# ASD2163.net
KiCad netlist of a schematic drawn in EAGLE
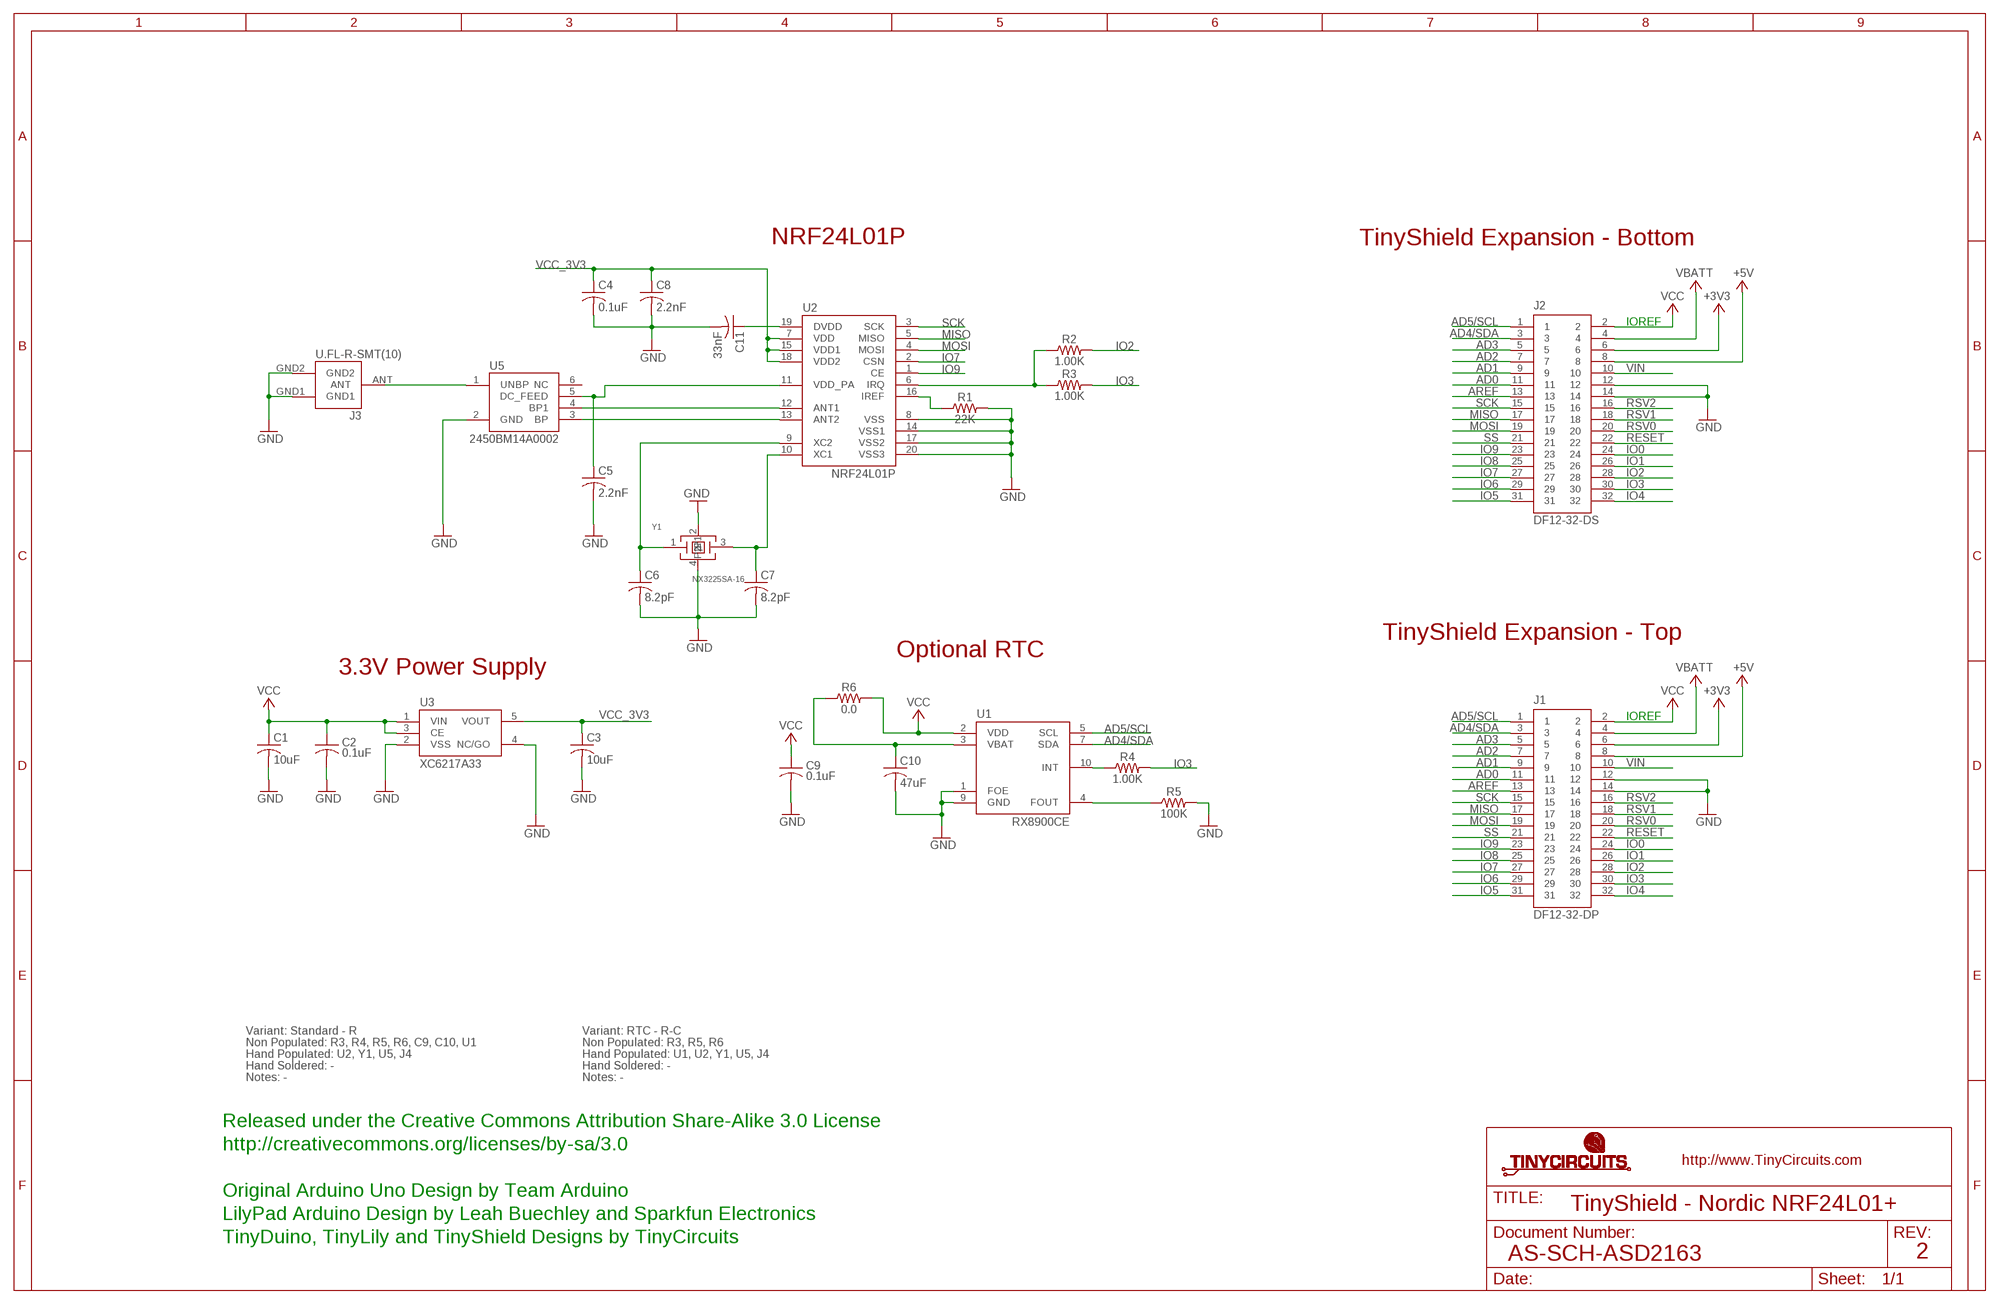
[diagram p0: schematic, sheet 1]

(export (version "E")
  (design (tool "Eeschema 10.0.6"))
  (components
    (comp (ref "C1")
      (value "10uF")
      (footprint "eagle-import:C0603")
      (fields (field (name "PARTNO") "AS-ITM-00002") (field (name "PARTNO_1") "AS-ITM-00002"))
      (libsource (lib "eagle-import") (part "AS-ITM-00002"))
    )
    (comp (ref "C2")
      (value "0.1uF")
      (footprint "eagle-import:C0402")
      (fields (field (name "PARTNO") "AS-ITM-00008") (field (name "PARTNO_1") "AS-ITM-00008"))
      (libsource (lib "eagle-import") (part "AS-ITM-00008"))
    )
    (comp (ref "C3")
      (value "10uF")
      (footprint "eagle-import:C0603")
      (fields (field (name "PARTNO") "AS-ITM-00002") (field (name "PARTNO_1") "AS-ITM-00002"))
      (libsource (lib "eagle-import") (part "AS-ITM-00002"))
    )
    (comp (ref "C4")
      (value "0.1uF")
      (footprint "eagle-import:C0402")
      (fields (field (name "PARTNO") "AS-ITM-00008") (field (name "PARTNO_1") "AS-ITM-00008"))
      (libsource (lib "eagle-import") (part "AS-ITM-00008"))
    )
    (comp (ref "C5")
      (value "2.2nF")
      (footprint "eagle-import:C0402")
      (fields (field (name "PARTNO") "AS-ITM-00085"))
      (libsource (lib "eagle-import") (part "AS-ITM-00085"))
    )
    (comp (ref "C6")
      (value "8.2pF")
      (footprint "eagle-import:C0402")
      (fields (field (name "PARTNO") "AS-ITM-00247") (field (name "PARTNO_1") "AS-ITM-00247"))
      (libsource (lib "eagle-import") (part "AS-ITM-00247"))
    )
    (comp (ref "C7")
      (value "8.2pF")
      (footprint "eagle-import:C0402")
      (fields (field (name "PARTNO") "AS-ITM-00247") (field (name "PARTNO_1") "AS-ITM-00247"))
      (libsource (lib "eagle-import") (part "AS-ITM-00247"))
    )
    (comp (ref "C8")
      (value "2.2nF")
      (footprint "eagle-import:C0402")
      (fields (field (name "PARTNO") "AS-ITM-00085") (field (name "PARTNO_1") "AS-ITM-00085"))
      (libsource (lib "eagle-import") (part "AS-ITM-00085"))
    )
    (comp (ref "C9")
      (value "0.1uF")
      (footprint "eagle-import:C0402")
      (fields (field (name "PARTNO") "AS-ITM-00008") (field (name "PARTNO_1") "AS-ITM-00008"))
      (libsource (lib "eagle-import") (part "AS-ITM-00008"))
    )
    (comp (ref "C10")
      (value "47uF")
      (footprint "eagle-import:C1206")
      (fields (field (name "PARTNO") "AS-ITM-00049"))
      (libsource (lib "eagle-import") (part "AS-ITM-00049"))
    )
    (comp (ref "C11")
      (value "33nF")
      (footprint "eagle-import:C0402")
      (fields (field (name "PARTNO") "AS-ITM-00248") (field (name "PARTNO_1") "AS-ITM-00248"))
      (libsource (lib "eagle-import") (part "AS-ITM-00248"))
    )
    (comp (ref "J1")
      (value "DF12-32-DP")
      (footprint "eagle-import:DF12-32-DP")
      (fields (field (name "PARTNO") "AS-ITM-00015") (field (name "PARTNO_1") "AS-ITM-00015"))
      (libsource (lib "eagle-import") (part "AS-ITM-00015"))
    )
    (comp (ref "J2")
      (value "DF12-32-DS")
      (footprint "eagle-import:DF12-32-DS")
      (fields (field (name "PARTNO") "AS-ITM-00012") (field (name "PARTNO_1") "AS-ITM-00012"))
      (libsource (lib "eagle-import") (part "AS-ITM-00012"))
    )
    (comp (ref "J3")
      (value "U.FL-R-SMT(10)")
      (footprint "eagle-import:U.FL-R-SMT(10)")
      (fields (field (name "PARTNO") "AS-ITM-00193"))
      (libsource (lib "eagle-import") (part "AS-ITM-00193"))
    )
    (comp (ref "R1")
      (value "22K")
      (footprint "eagle-import:0402")
      (fields (field (name "PARTNO") "AS-ITM-00147"))
      (libsource (lib "eagle-import") (part "AS-ITM-00147"))
    )
    (comp (ref "R2")
      (value "1.00K")
      (footprint "eagle-import:0402")
      (fields (field (name "PARTNO") "AS-ITM-00003") (field (name "PARTNO_1") "AS-ITM-00003"))
      (libsource (lib "eagle-import") (part "AS-ITM-00003"))
    )
    (comp (ref "R3")
      (value "1.00K")
      (footprint "eagle-import:0402")
      (fields (field (name "PARTNO") "AS-ITM-00003") (field (name "PARTNO_1") "AS-ITM-00003"))
      (libsource (lib "eagle-import") (part "AS-ITM-00003"))
    )
    (comp (ref "R4")
      (value "1.00K")
      (footprint "eagle-import:0402")
      (fields (field (name "PARTNO") "AS-ITM-00003") (field (name "PARTNO_1") "AS-ITM-00003"))
      (libsource (lib "eagle-import") (part "AS-ITM-00003"))
    )
    (comp (ref "R5")
      (value "100K")
      (footprint "eagle-import:0402")
      (fields (field (name "PARTNO") "AS-ITM-00004"))
      (libsource (lib "eagle-import") (part "AS-ITM-00004"))
    )
    (comp (ref "R6")
      (value "0.0")
      (footprint "eagle-import:0402")
      (fields (field (name "PARTNO") "AS-ITM-00076") (field (name "PARTNO_1") "AS-ITM-00076"))
      (libsource (lib "eagle-import") (part "AS-ITM-00076"))
    )
    (comp (ref "U1")
      (value "RX8900CE")
      (footprint "eagle-import:RX8900CE")
      (fields (field (name "PARTNO") "AS-ITM-00373"))
      (libsource (lib "eagle-import") (part "AS-ITM-00373"))
    )
    (comp (ref "U2")
      (value "NRF24L01P")
      (footprint "eagle-import:QFN20-NO_PAD")
      (fields (field (name "PARTNO") "AS-ITM-00276"))
      (libsource (lib "eagle-import") (part "AS-ITM-00276"))
    )
    (comp (ref "U3")
      (value "XC6217A33")
      (footprint "eagle-import:SOT-25")
      (fields (field (name "PARTNO") "AS-ITM-00249") (field (name "PARTNO_1") "AS-ITM-00249"))
      (libsource (lib "eagle-import") (part "AS-ITM-00249"))
    )
    (comp (ref "U5")
      (value "2450BM14A0002")
      (footprint "eagle-import:2450BM14A0002")
      (fields (field (name "PARTNO") "AS-ITM-00114"))
      (libsource (lib "eagle-import") (part "AS-ITM-00114"))
    )
    (comp (ref "Y1")
      (value "NX3225SA-16")
      (footprint "eagle-import:ABM11")
      (fields (field (name "PARTNO") "AS-ITM-00228") (field (name "PARTNO_1") "AS-ITM-00228"))
      (libsource (lib "eagle-import") (part "AS-ITM-00228"))
    )
  )
  (nets
    (net (code "1") (name "+3V3") (class "Default")
      (node (ref "J1") (pin "6") (pinfunction "6_6") (pintype "bidirectional"))
      (node (ref "J2") (pin "6") (pinfunction "6_6") (pintype "bidirectional"))
    )
    (net (code "2") (name "+5V") (class "Default")
      (node (ref "J1") (pin "8") (pinfunction "8_8") (pintype "bidirectional"))
      (node (ref "J2") (pin "8") (pinfunction "8_8") (pintype "bidirectional"))
    )
    (net (code "3") (name "/AD0") (class "Default")
      (node (ref "J1") (pin "11") (pinfunction "11_11") (pintype "bidirectional"))
      (node (ref "J2") (pin "11") (pinfunction "11_11") (pintype "bidirectional"))
    )
    (net (code "4") (name "/AD1") (class "Default")
      (node (ref "J1") (pin "9") (pinfunction "9_9") (pintype "bidirectional"))
      (node (ref "J2") (pin "9") (pinfunction "9_9") (pintype "bidirectional"))
    )
    (net (code "5") (name "/AD2") (class "Default")
      (node (ref "J1") (pin "7") (pinfunction "7_7") (pintype "bidirectional"))
      (node (ref "J2") (pin "7") (pinfunction "7_7") (pintype "bidirectional"))
    )
    (net (code "6") (name "/AD3") (class "Default")
      (node (ref "J1") (pin "5") (pinfunction "5_5") (pintype "bidirectional"))
      (node (ref "J2") (pin "5") (pinfunction "5_5") (pintype "bidirectional"))
    )
    (net (code "7") (name "/AD4{slash}SDA") (class "Default")
      (node (ref "J1") (pin "3") (pinfunction "3_3") (pintype "bidirectional"))
      (node (ref "J2") (pin "3") (pinfunction "3_3") (pintype "bidirectional"))
      (node (ref "U1") (pin "7") (pinfunction "SDA_7") (pintype "bidirectional"))
    )
    (net (code "8") (name "/AD5{slash}SCL") (class "Default")
      (node (ref "J1") (pin "1") (pinfunction "1_1") (pintype "bidirectional"))
      (node (ref "J2") (pin "1") (pinfunction "1_1") (pintype "bidirectional"))
      (node (ref "U1") (pin "5") (pinfunction "SCL_5") (pintype "bidirectional"))
    )
    (net (code "9") (name "/AREF") (class "Default")
      (node (ref "J1") (pin "13") (pinfunction "13_13") (pintype "bidirectional"))
      (node (ref "J2") (pin "13") (pinfunction "13_13") (pintype "bidirectional"))
    )
    (net (code "10") (name "/IO0") (class "Default")
      (node (ref "J1") (pin "24") (pinfunction "24_24") (pintype "bidirectional"))
      (node (ref "J2") (pin "24") (pinfunction "24_24") (pintype "bidirectional"))
    )
    (net (code "11") (name "/IO1") (class "Default")
      (node (ref "J1") (pin "26") (pinfunction "26_26") (pintype "bidirectional"))
      (node (ref "J2") (pin "26") (pinfunction "26_26") (pintype "bidirectional"))
    )
    (net (code "12") (name "/IO2") (class "Default")
      (node (ref "J1") (pin "28") (pinfunction "28_28") (pintype "bidirectional"))
      (node (ref "J2") (pin "28") (pinfunction "28_28") (pintype "bidirectional"))
      (node (ref "R2") (pin "2") (pinfunction "2_2") (pintype "passive"))
    )
    (net (code "13") (name "/IO3") (class "Default")
      (node (ref "J1") (pin "30") (pinfunction "30_30") (pintype "bidirectional"))
      (node (ref "J2") (pin "30") (pinfunction "30_30") (pintype "bidirectional"))
      (node (ref "R3") (pin "2") (pinfunction "2_2") (pintype "passive"))
      (node (ref "R4") (pin "2") (pinfunction "2_2") (pintype "passive"))
    )
    (net (code "14") (name "/IO4") (class "Default")
      (node (ref "J1") (pin "32") (pinfunction "32_32") (pintype "bidirectional"))
      (node (ref "J2") (pin "32") (pinfunction "32_32") (pintype "bidirectional"))
    )
    (net (code "15") (name "/IO5") (class "Default")
      (node (ref "J1") (pin "31") (pinfunction "31_31") (pintype "bidirectional"))
      (node (ref "J2") (pin "31") (pinfunction "31_31") (pintype "bidirectional"))
    )
    (net (code "16") (name "/IO6") (class "Default")
      (node (ref "J1") (pin "29") (pinfunction "29_29") (pintype "bidirectional"))
      (node (ref "J2") (pin "29") (pinfunction "29_29") (pintype "bidirectional"))
    )
    (net (code "17") (name "/IO7") (class "Default")
      (node (ref "J1") (pin "27") (pinfunction "27_27") (pintype "bidirectional"))
      (node (ref "J2") (pin "27") (pinfunction "27_27") (pintype "bidirectional"))
      (node (ref "U2") (pin "2") (pinfunction "CSN_2") (pintype "bidirectional"))
    )
    (net (code "18") (name "/IO8") (class "Default")
      (node (ref "J1") (pin "25") (pinfunction "25_25") (pintype "bidirectional"))
      (node (ref "J2") (pin "25") (pinfunction "25_25") (pintype "bidirectional"))
    )
    (net (code "19") (name "/IO9") (class "Default")
      (node (ref "J1") (pin "23") (pinfunction "23_23") (pintype "bidirectional"))
      (node (ref "J2") (pin "23") (pinfunction "23_23") (pintype "bidirectional"))
      (node (ref "U2") (pin "1") (pinfunction "CE_1") (pintype "bidirectional"))
    )
    (net (code "20") (name "/MISO") (class "Default")
      (node (ref "J1") (pin "17") (pinfunction "17_17") (pintype "bidirectional"))
      (node (ref "J2") (pin "17") (pinfunction "17_17") (pintype "bidirectional"))
      (node (ref "U2") (pin "5") (pinfunction "MISO_5") (pintype "bidirectional"))
    )
    (net (code "21") (name "/MOSI") (class "Default")
      (node (ref "J1") (pin "19") (pinfunction "19_19") (pintype "bidirectional"))
      (node (ref "J2") (pin "19") (pinfunction "19_19") (pintype "bidirectional"))
      (node (ref "U2") (pin "4") (pinfunction "MOSI_4") (pintype "bidirectional"))
    )
    (net (code "22") (name "/RESET") (class "Default")
      (node (ref "J1") (pin "22") (pinfunction "22_22") (pintype "bidirectional"))
      (node (ref "J2") (pin "22") (pinfunction "22_22") (pintype "bidirectional"))
    )
    (net (code "23") (name "/RSV0") (class "Default")
      (node (ref "J1") (pin "20") (pinfunction "20_20") (pintype "bidirectional"))
      (node (ref "J2") (pin "20") (pinfunction "20_20") (pintype "bidirectional"))
    )
    (net (code "24") (name "/RSV1") (class "Default")
      (node (ref "J1") (pin "18") (pinfunction "18_18") (pintype "bidirectional"))
      (node (ref "J2") (pin "18") (pinfunction "18_18") (pintype "bidirectional"))
    )
    (net (code "25") (name "/RSV2") (class "Default")
      (node (ref "J1") (pin "16") (pinfunction "16_16") (pintype "bidirectional"))
      (node (ref "J2") (pin "16") (pinfunction "16_16") (pintype "bidirectional"))
    )
    (net (code "26") (name "/SCK") (class "Default")
      (node (ref "J1") (pin "15") (pinfunction "15_15") (pintype "bidirectional"))
      (node (ref "J2") (pin "15") (pinfunction "15_15") (pintype "bidirectional"))
      (node (ref "U2") (pin "3") (pinfunction "SCK_3") (pintype "bidirectional"))
    )
    (net (code "27") (name "/SS") (class "Default")
      (node (ref "J1") (pin "21") (pinfunction "21_21") (pintype "bidirectional"))
      (node (ref "J2") (pin "21") (pinfunction "21_21") (pintype "bidirectional"))
    )
    (net (code "28") (name "/VCC_3V3") (class "Default")
      (node (ref "C3") (pin "1") (pinfunction "1_1") (pintype "passive"))
      (node (ref "C4") (pin "1") (pinfunction "1_1") (pintype "passive"))
      (node (ref "C8") (pin "1") (pinfunction "1_1") (pintype "passive"))
      (node (ref "U2") (pin "15") (pinfunction "VDD1_15") (pintype "bidirectional"))
      (node (ref "U2") (pin "18") (pinfunction "VDD2_18") (pintype "bidirectional"))
      (node (ref "U2") (pin "7") (pinfunction "VDD_7") (pintype "bidirectional"))
      (node (ref "U3") (pin "5") (pinfunction "VOUT_5") (pintype "bidirectional"))
    )
    (net (code "29") (name "/VIN") (class "Default")
      (node (ref "J1") (pin "10") (pinfunction "10_10") (pintype "bidirectional"))
      (node (ref "J2") (pin "10") (pinfunction "10_10") (pintype "bidirectional"))
    )
    (net (code "30") (name "GND") (class "Default")
      (node (ref "C1") (pin "2") (pinfunction "2_2") (pintype "passive"))
      (node (ref "C10") (pin "2") (pinfunction "2_2") (pintype "passive"))
      (node (ref "C11") (pin "2") (pinfunction "2_2") (pintype "passive"))
      (node (ref "C2") (pin "2") (pinfunction "2_2") (pintype "passive"))
      (node (ref "C3") (pin "2") (pinfunction "2_2") (pintype "passive"))
      (node (ref "C4") (pin "2") (pinfunction "2_2") (pintype "passive"))
      (node (ref "C5") (pin "2") (pinfunction "2_2") (pintype "passive"))
      (node (ref "C6") (pin "2") (pinfunction "2_2") (pintype "passive"))
      (node (ref "C7") (pin "2") (pinfunction "2_2") (pintype "passive"))
      (node (ref "C8") (pin "2") (pinfunction "2_2") (pintype "passive"))
      (node (ref "C9") (pin "2") (pinfunction "2_2") (pintype "passive"))
      (node (ref "J1") (pin "12") (pinfunction "12_12") (pintype "bidirectional"))
      (node (ref "J1") (pin "14") (pinfunction "14_14") (pintype "bidirectional"))
      (node (ref "J2") (pin "12") (pinfunction "12_12") (pintype "bidirectional"))
      (node (ref "J2") (pin "14") (pinfunction "14_14") (pintype "bidirectional"))
      (node (ref "J3") (pin "GND1") (pinfunction "GND1_GND1") (pintype "bidirectional"))
      (node (ref "J3") (pin "GND2") (pinfunction "GND2_GND2") (pintype "bidirectional"))
      (node (ref "R1") (pin "2") (pinfunction "2_2") (pintype "passive"))
      (node (ref "R5") (pin "2") (pinfunction "2_2") (pintype "passive"))
      (node (ref "U1") (pin "1") (pinfunction "FOE_1") (pintype "bidirectional"))
      (node (ref "U1") (pin "9") (pinfunction "GND_9") (pintype "bidirectional"))
      (node (ref "U2") (pin "14") (pinfunction "VSS1_14") (pintype "bidirectional"))
      (node (ref "U2") (pin "17") (pinfunction "VSS2_17") (pintype "bidirectional"))
      (node (ref "U2") (pin "20") (pinfunction "VSS3_20") (pintype "bidirectional"))
      (node (ref "U2") (pin "8") (pinfunction "VSS_8") (pintype "bidirectional"))
      (node (ref "U3") (pin "2") (pinfunction "VSS_2") (pintype "power_in"))
      (node (ref "U3") (pin "4") (pinfunction "NC/GO_4") (pintype "bidirectional"))
      (node (ref "U5") (pin "2") (pinfunction "GND_2") (pintype "bidirectional"))
      (node (ref "Y1") (pin "2") (pinfunction "P2_2") (pintype "bidirectional"))
      (node (ref "Y1") (pin "4") (pinfunction "P1_4") (pintype "bidirectional"))
    )
    (net (code "31") (name "Net-(U1-FOUT)") (class "Default")
      (node (ref "R5") (pin "1") (pinfunction "1_1") (pintype "passive"))
      (node (ref "U1") (pin "4") (pinfunction "FOUT_4") (pintype "bidirectional"))
    )
    (net (code "32") (name "Net-(U1-INT)") (class "Default")
      (node (ref "R4") (pin "1") (pinfunction "1_1") (pintype "passive"))
      (node (ref "U1") (pin "10") (pinfunction "INT_10") (pintype "bidirectional"))
    )
    (net (code "33") (name "Net-(U1-VBAT)") (class "Default")
      (node (ref "C10") (pin "1") (pinfunction "1_1") (pintype "passive"))
      (node (ref "R6") (pin "1") (pinfunction "1_1") (pintype "passive"))
      (node (ref "U1") (pin "3") (pinfunction "VBAT_3") (pintype "bidirectional"))
    )
    (net (code "34") (name "Net-(U2-ANT1)") (class "Default")
      (node (ref "U2") (pin "12") (pinfunction "ANT1_12") (pintype "bidirectional"))
      (node (ref "U5") (pin "4") (pinfunction "BP1_4") (pintype "bidirectional"))
    )
    (net (code "35") (name "Net-(U2-ANT2)") (class "Default")
      (node (ref "U2") (pin "13") (pinfunction "ANT2_13") (pintype "bidirectional"))
      (node (ref "U5") (pin "3") (pinfunction "BP_3") (pintype "bidirectional"))
    )
    (net (code "36") (name "Net-(U2-DVDD)") (class "Default")
      (node (ref "C11") (pin "1") (pinfunction "1_1") (pintype "passive"))
      (node (ref "U2") (pin "19") (pinfunction "DVDD_19") (pintype "bidirectional"))
    )
    (net (code "37") (name "Net-(U2-IREF)") (class "Default")
      (node (ref "R1") (pin "1") (pinfunction "1_1") (pintype "passive"))
      (node (ref "U2") (pin "16") (pinfunction "IREF_16") (pintype "bidirectional"))
    )
    (net (code "38") (name "Net-(U2-IRQ)") (class "Default")
      (node (ref "R2") (pin "1") (pinfunction "1_1") (pintype "passive"))
      (node (ref "R3") (pin "1") (pinfunction "1_1") (pintype "passive"))
      (node (ref "U2") (pin "6") (pinfunction "IRQ_6") (pintype "bidirectional"))
    )
    (net (code "39") (name "Net-(U2-VDD_PA)") (class "Default")
      (node (ref "C5") (pin "1") (pinfunction "1_1") (pintype "passive"))
      (node (ref "U2") (pin "11") (pinfunction "VDD_PA_11") (pintype "bidirectional"))
      (node (ref "U5") (pin "5") (pinfunction "DC_FEED_5") (pintype "bidirectional"))
    )
    (net (code "40") (name "Net-(U2-XC1)") (class "Default")
      (node (ref "C7") (pin "1") (pinfunction "1_1") (pintype "passive"))
      (node (ref "U2") (pin "10") (pinfunction "XC1_10") (pintype "bidirectional"))
      (node (ref "Y1") (pin "3") (pinfunction "2_3") (pintype "bidirectional"))
    )
    (net (code "41") (name "Net-(U2-XC2)") (class "Default")
      (node (ref "C6") (pin "1") (pinfunction "1_1") (pintype "passive"))
      (node (ref "U2") (pin "9") (pinfunction "XC2_9") (pintype "bidirectional"))
      (node (ref "Y1") (pin "1") (pinfunction "1_1") (pintype "bidirectional"))
    )
    (net (code "42") (name "Net-(U5-UNBP)") (class "Default")
      (node (ref "J3") (pin "ANT") (pinfunction "ANT_ANT") (pintype "bidirectional"))
      (node (ref "U5") (pin "1") (pinfunction "UNBP_1") (pintype "bidirectional"))
    )
    (net (code "43") (name "VBATT") (class "Default")
      (node (ref "J1") (pin "4") (pinfunction "4_4") (pintype "bidirectional"))
      (node (ref "J2") (pin "4") (pinfunction "4_4") (pintype "bidirectional"))
    )
    (net (code "44") (name "VCC") (class "Default")
      (node (ref "C1") (pin "1") (pinfunction "1_1") (pintype "passive"))
      (node (ref "C2") (pin "1") (pinfunction "1_1") (pintype "passive"))
      (node (ref "C9") (pin "1") (pinfunction "1_1") (pintype "passive"))
      (node (ref "J1") (pin "2") (pinfunction "2_2") (pintype "bidirectional"))
      (node (ref "J2") (pin "2") (pinfunction "2_2") (pintype "bidirectional"))
      (node (ref "R6") (pin "2") (pinfunction "2_2") (pintype "passive"))
      (node (ref "U1") (pin "2") (pinfunction "VDD_2") (pintype "bidirectional"))
      (node (ref "U3") (pin "1") (pinfunction "VIN_1") (pintype "bidirectional"))
      (node (ref "U3") (pin "3") (pinfunction "CE_3") (pintype "bidirectional"))
    )
    (net (code "45") (name "unconnected-(U5-NC-Pad6)") (class "Default")
      (node (ref "U5") (pin "6") (pinfunction "NC_6") (pintype "bidirectional"))
    )
  )
)
